# ADC.net
KiCad netlist of a schematic drawn in Altium Designer
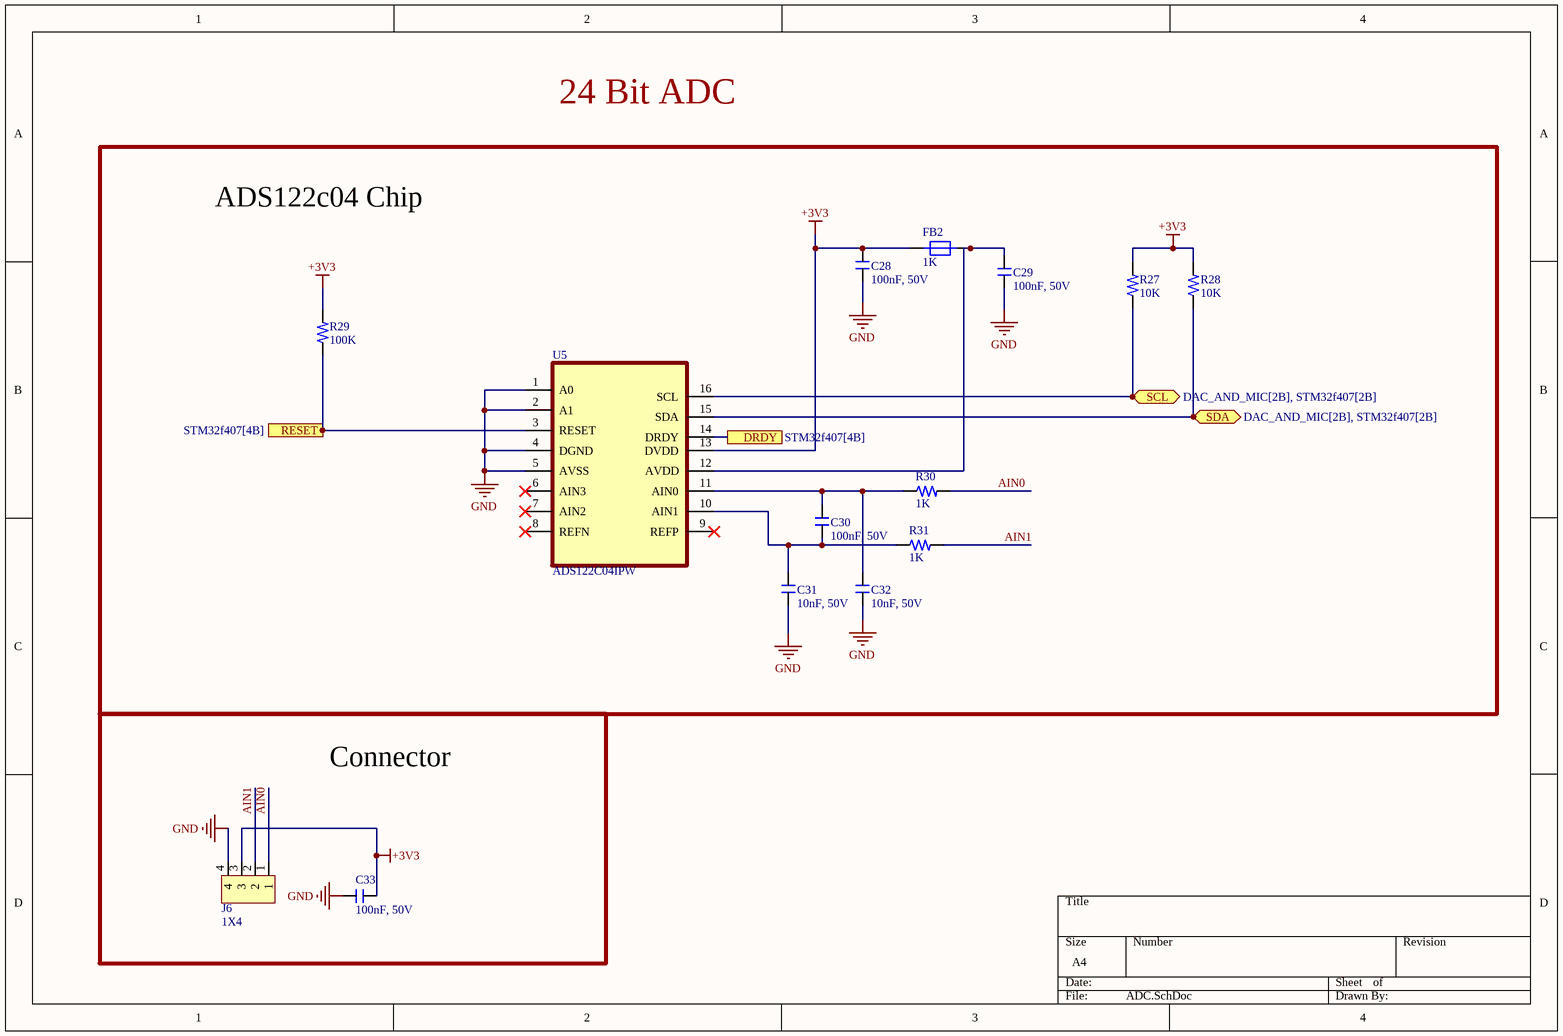
[diagram p0: ADC.SchDoc]

(export (version "E")
  (design (tool "Eeschema 10.0.6"))
  (components
    (comp (ref "C28")
      (value "100nF, 50V")
      (footprint "Capacitor_0805")
      (description "Multilayer Ceramic Capacitor, 0.1 uF, 50 V, ï¿½ 10%, X7R, 0805 [2012 Metric]")
      (fields
        (field (name "MANUFACTURER") "Samsung")
        (field (name "MANUFACTURER PART NUMBER") "CL21B104KBCNNNC")
      )
      (libsource (lib "Schematics_Library_Hanif") (part "Cap_100nF_0805"))
    )
    (comp (ref "C29")
      (value "100nF, 50V")
      (footprint "Capacitor_0805")
      (description "Multilayer Ceramic Capacitor, 0.1 uF, 50 V, ï¿½ 10%, X7R, 0805 [2012 Metric]")
      (fields
        (field (name "MANUFACTURER") "Samsung")
        (field (name "MANUFACTURER PART NUMBER") "CL21B104KBCNNNC")
      )
      (libsource (lib "Schematics_Library_Hanif") (part "Cap_100nF_0805"))
    )
    (comp (ref "C30")
      (value "100nF, 50V")
      (footprint "Capacitor_0805")
      (description "Multilayer Ceramic Capacitor, 0.1 uF, 50 V, ï¿½ 10%, X7R, 0805 [2012 Metric]")
      (fields
        (field (name "MANUFACTURER") "Samsung")
        (field (name "MANUFACTURER PART NUMBER") "CL21B104KBCNNNC")
      )
      (libsource (lib "Schematics_Library_Hanif") (part "Cap_100nF_0805"))
    )
    (comp (ref "C31")
      (value "10nF, 50V")
      (footprint "Capacitor_0805")
      (description "Multilayer Ceramic Capacitors MLCC - SMD/SMT 50V 0.01uF X7R 0805 10% AEC-Q200")
      (fields
        (field (name "MANUFACTURER") "KEMET")
        (field (name "MANUFACTURER PART NUMBER") "C0805C103K5RECAUTO")
      )
      (libsource (lib "Schematics_Library_Hanif") (part "Cap_10nF_0805"))
    )
    (comp (ref "C32")
      (value "10nF, 50V")
      (footprint "Capacitor_0805")
      (description "Multilayer Ceramic Capacitors MLCC - SMD/SMT 50V 0.01uF X7R 0805 10% AEC-Q200")
      (fields
        (field (name "MANUFACTURER") "KEMET")
        (field (name "MANUFACTURER PART NUMBER") "C0805C103K5RECAUTO")
      )
      (libsource (lib "Schematics_Library_Hanif") (part "Cap_10nF_0805"))
    )
    (comp (ref "C33")
      (value "100nF, 50V")
      (footprint "Capacitor_0805")
      (description "Multilayer Ceramic Capacitor, 0.1 uF, 50 V, ï¿½ 10%, X7R, 0805 [2012 Metric]")
      (fields
        (field (name "MANUFACTURER") "Samsung")
        (field (name "MANUFACTURER PART NUMBER") "CL21B104KBCNNNC")
      )
      (libsource (lib "Schematics_Library_Hanif") (part "Cap_100nF_0805"))
    )
    (comp (ref "FB2")
      (value "1K")
      (footprint "FB_0805")
      (description "Ferrite Beads Multi-Layer High Current 1KOhm 25% 100MHz 1.6A 0.12Ohm DCR 0805 Automotive T/R")
      (fields
        (field (name "MANUFACTURER") "Murata")
        (field (name "MANUFACTURER PART NUMBER") "BLM21SP102SH1D")
      )
      (libsource (lib "Schematics_Library_Hanif") (part "FB_BLM21SP102SH1D"))
    )
    (comp (ref "J6")
      (value "1X4")
      (footprint "Header_1X4_2.54mm")
      (description "THT Vertical Pin Header WR-PHD, Pitch 2.54 mm, Single Row, 4 pins")
      (fields
        (field (name "MANUFACTURER") "Wurth Electronics")
        (field (name "MANUFACTURER PART NUMBER") "61300411121")
      )
      (libsource (lib "Schematics_Library_Hanif") (part "Header_Male_1X4_2.54"))
    )
    (comp (ref "R27")
      (value "10K")
      (footprint "Resistor_0603")
      (description "SMD Chip Resistor, 10 kOhm, ï¿½ 1%, 100 mW, 0603 [1608 Metric], Thick Film, General Purpose")
      (fields
        (field (name "MANUFACTURER") "Yageo")
        (field (name "MANUFACTURER PART NUMBER") "RC0603FR-0710KL")
      )
      (libsource (lib "Schematics_Library_Hanif") (part "R_10K_0603"))
    )
    (comp (ref "R28")
      (value "10K")
      (footprint "Resistor_0603")
      (description "SMD Chip Resistor, 10 kOhm, ï¿½ 1%, 100 mW, 0603 [1608 Metric], Thick Film, General Purpose")
      (fields
        (field (name "MANUFACTURER") "Yageo")
        (field (name "MANUFACTURER PART NUMBER") "RC0603FR-0710KL")
      )
      (libsource (lib "Schematics_Library_Hanif") (part "R_10K_0603"))
    )
    (comp (ref "R29")
      (value "100K")
      (footprint "Resistor_0603")
      (description "Res Thick Film 0603 100K Ohm 1% 0.1W(1/10W) ±100ppm/C Pad SMD Automotive T/R")
      (fields
        (field (name "MANUFACTURER") "Stackpole Electronics")
        (field (name "MANUFACTURER PART NUMBER") "RMCF0603FT100K")
      )
      (libsource (lib "Schematics_Library_Hanif") (part "R_100K_0603"))
    )
    (comp (ref "R30")
      (value "1K")
      (footprint "Resistor_0603")
      (description "Res Thick Film 0603 1K Ohm 1% 0.1W(1/10W) ±100ppm/C Pad SMD T/R")
      (fields
        (field (name "MANUFACTURER") "Walsin Technologies")
        (field (name "MANUFACTURER PART NUMBER") "WR06X1001FTL")
      )
      (libsource (lib "Schematics_Library_Hanif") (part "R_1k_0603"))
    )
    (comp (ref "R31")
      (value "1K")
      (footprint "Resistor_0603")
      (description "Res Thick Film 0603 1K Ohm 1% 0.1W(1/10W) ±100ppm/C Pad SMD T/R")
      (fields
        (field (name "MANUFACTURER") "Walsin Technologies")
        (field (name "MANUFACTURER PART NUMBER") "WR06X1001FTL")
      )
      (libsource (lib "Schematics_Library_Hanif") (part "R_1k_0603"))
    )
    (comp (ref "U5")
      (value "ADS122C04IPW")
      (footprint "16_TSSOP")
      (description "ADC Quad Delta-Sigma 2ksps 24-bit Serial (I2C) 16-Pin TSSOP Tube")
      (fields (field (name "MANUFACTURER") "Texas Instruments"))
      (libsource (lib "Schematics_Library_Hanif") (part "IC_ADC_ADS122C04IPW"))
    )
  )
  (nets
    (net (code "1") (name "+3V3") (class "Default")
      (node (ref "C28") (pin "2") (pinfunction "2_2") (pintype "passive"))
      (node (ref "C33") (pin "2") (pinfunction "2_2") (pintype "passive"))
      (node (ref "FB2") (pin "1") (pinfunction "1_1") (pintype "passive"))
      (node (ref "J6") (pin "3") (pinfunction "3_3") (pintype "passive"))
      (node (ref "R27") (pin "2") (pinfunction "2_2") (pintype "passive"))
      (node (ref "R28") (pin "2") (pinfunction "2_2") (pintype "passive"))
      (node (ref "R29") (pin "2") (pinfunction "2_2") (pintype "passive"))
      (node (ref "U5") (pin "13") (pinfunction "DVDD_13") (pintype "passive"))
    )
    (net (code "2") (name "/AIN0") (class "Default")
      (node (ref "J6") (pin "1") (pinfunction "1_1") (pintype "passive"))
      (node (ref "R30") (pin "2") (pinfunction "2_2") (pintype "passive"))
    )
    (net (code "3") (name "/AIN1") (class "Default")
      (node (ref "J6") (pin "2") (pinfunction "2_2") (pintype "passive"))
      (node (ref "R31") (pin "2") (pinfunction "2_2") (pintype "passive"))
    )
    (net (code "4") (name "/DRDY") (class "Default")
      (node (ref "U5") (pin "14") (pinfunction "DRDY_14") (pintype "passive"))
    )
    (net (code "5") (name "/RESET") (class "Default")
      (node (ref "R29") (pin "1") (pinfunction "1_1") (pintype "passive"))
      (node (ref "U5") (pin "3") (pinfunction "RESET_3") (pintype "passive"))
    )
    (net (code "6") (name "/SCL") (class "Default")
      (node (ref "R27") (pin "1") (pinfunction "1_1") (pintype "passive"))
      (node (ref "U5") (pin "16") (pinfunction "SCL_16") (pintype "passive"))
    )
    (net (code "7") (name "/SDA") (class "Default")
      (node (ref "R28") (pin "1") (pinfunction "1_1") (pintype "passive"))
      (node (ref "U5") (pin "15") (pinfunction "SDA_15") (pintype "passive"))
    )
    (net (code "8") (name "GND") (class "Default")
      (node (ref "C28") (pin "1") (pinfunction "1_1") (pintype "passive"))
      (node (ref "C29") (pin "1") (pinfunction "1_1") (pintype "passive"))
      (node (ref "C31") (pin "1") (pinfunction "1_1") (pintype "passive"))
      (node (ref "C32") (pin "1") (pinfunction "1_1") (pintype "passive"))
      (node (ref "C33") (pin "1") (pinfunction "1_1") (pintype "passive"))
      (node (ref "J6") (pin "4") (pinfunction "4_4") (pintype "passive"))
      (node (ref "U5") (pin "1") (pinfunction "A0_1") (pintype "passive"))
      (node (ref "U5") (pin "2") (pinfunction "A1_2") (pintype "passive"))
      (node (ref "U5") (pin "4") (pinfunction "DGND_4") (pintype "passive"))
      (node (ref "U5") (pin "5") (pinfunction "AVSS_5") (pintype "passive"))
    )
    (net (code "9") (name "Net-(U5-AIN0)") (class "Default")
      (node (ref "C30") (pin "2") (pinfunction "2_2") (pintype "passive"))
      (node (ref "C32") (pin "2") (pinfunction "2_2") (pintype "passive"))
      (node (ref "R30") (pin "1") (pinfunction "1_1") (pintype "passive"))
      (node (ref "U5") (pin "11") (pinfunction "AIN0_11") (pintype "passive"))
    )
    (net (code "10") (name "Net-(U5-AIN1)") (class "Default")
      (node (ref "C30") (pin "1") (pinfunction "1_1") (pintype "passive"))
      (node (ref "C31") (pin "2") (pinfunction "2_2") (pintype "passive"))
      (node (ref "R31") (pin "1") (pinfunction "1_1") (pintype "passive"))
      (node (ref "U5") (pin "10") (pinfunction "AIN1_10") (pintype "passive"))
    )
    (net (code "11") (name "Net-(U5-AVDD)") (class "Default")
      (node (ref "C29") (pin "2") (pinfunction "2_2") (pintype "passive"))
      (node (ref "FB2") (pin "2") (pinfunction "2_2") (pintype "passive"))
      (node (ref "U5") (pin "12") (pinfunction "AVDD_12") (pintype "passive"))
    )
    (net (code "12") (name "unconnected-(U5-AIN2-Pad7)") (class "Default")
      (node (ref "U5") (pin "7") (pinfunction "AIN2_7") (pintype "passive+no_connect"))
    )
    (net (code "13") (name "unconnected-(U5-AIN3-Pad6)") (class "Default")
      (node (ref "U5") (pin "6") (pinfunction "AIN3_6") (pintype "passive+no_connect"))
    )
    (net (code "14") (name "unconnected-(U5-REFN-Pad8)") (class "Default")
      (node (ref "U5") (pin "8") (pinfunction "REFN_8") (pintype "passive+no_connect"))
    )
    (net (code "15") (name "unconnected-(U5-REFP-Pad9)") (class "Default")
      (node (ref "U5") (pin "9") (pinfunction "REFP_9") (pintype "passive+no_connect"))
    )
  )
)
